# hello44Leo.net
KiCad netlist of a schematic drawn in EAGLE
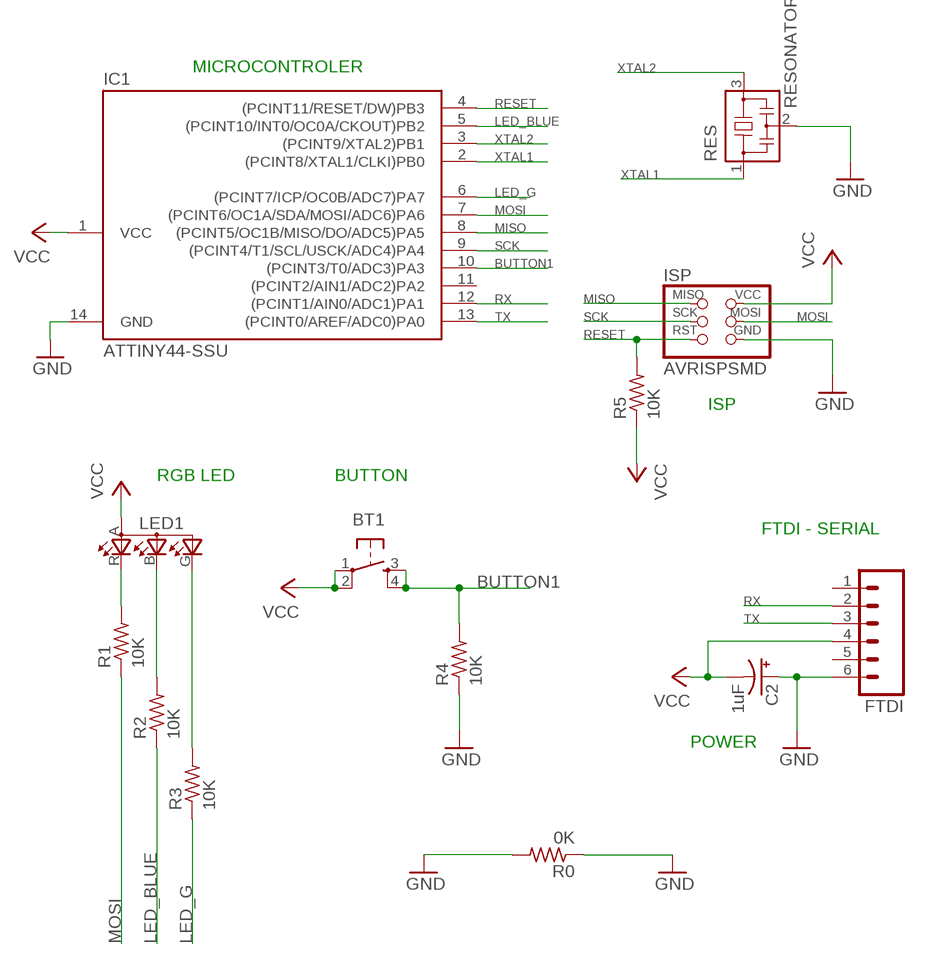
[diagram p0: schematic, sheet 1]

(export (version "E")
  (design (tool "Eeschema 10.0.6"))
  (components
    (comp (ref "BT1")
      (value "6MM_SWITCH6MM_SWITCH")
      (footprint "eagle-import:6MM_SWITCH")
      (libsource (lib "eagle-import") (part "6MM_SWITCH6MM_SWITCH"))
    )
    (comp (ref "C2")
      (value "1uF")
      (footprint "eagle-import:A3216-18")
      (libsource (lib "eagle-import") (part "POLARIZED_CAPACITORA3216-18"))
    )
    (comp (ref "FTDI")
      (value "M061X06-SMD_EDGE_FEMALE")
      (footprint "eagle-import:1X06-SMD_EDGE")
      (libsource (lib "eagle-import") (part "M061X06-SMD_EDGE_FEMALE"))
    )
    (comp (ref "IC1")
      (value "ATTINY44-SSU")
      (footprint "eagle-import:SOIC14")
      (libsource (lib "eagle-import") (part "ATTINY44-SSU"))
    )
    (comp (ref "ISP")
      (value "AVRISPSMD")
      (footprint "eagle-import:2X03SMD")
      (libsource (lib "eagle-import") (part "AVRISPSMD"))
    )
    (comp (ref "LED1")
      (value "LEDRGBOLD")
      (footprint "eagle-import:P-LCC-4-3")
      (libsource (lib "eagle-import") (part "LEDRGBOLD"))
    )
    (comp (ref "R0")
      (value "0K")
      (footprint "eagle-import:1206")
      (libsource (lib "eagle-import") (part "RESISTOR1206"))
    )
    (comp (ref "R1")
      (value "10K")
      (footprint "eagle-import:1206")
      (libsource (lib "eagle-import") (part "RESISTOR1206"))
    )
    (comp (ref "R2")
      (value "10K")
      (footprint "eagle-import:1206")
      (libsource (lib "eagle-import") (part "RESISTOR1206"))
    )
    (comp (ref "R3")
      (value "10K")
      (footprint "eagle-import:1206")
      (libsource (lib "eagle-import") (part "RESISTOR1206"))
    )
    (comp (ref "R4")
      (value "10K")
      (footprint "eagle-import:1206")
      (libsource (lib "eagle-import") (part "RESISTOR1206"))
    )
    (comp (ref "R5")
      (value "10K")
      (footprint "eagle-import:1206")
      (libsource (lib "eagle-import") (part "RESISTOR1206"))
    )
    (comp (ref "RES")
      (value "RESONATOR")
      (footprint "eagle-import:EFOBM")
      (libsource (lib "eagle-import") (part "RESONATOR"))
    )
  )
  (nets
    (net (code "1") (name "/BUTTON1") (class "Default")
      (node (ref "BT1") (pin "3") (pinfunction "S_3") (pintype "passive"))
      (node (ref "BT1") (pin "4") (pinfunction "S1_4") (pintype "passive"))
      (node (ref "IC1") (pin "10") (pinfunction "(PCINT3/T0/ADC3)PA3_10") (pintype "bidirectional"))
      (node (ref "R4") (pin "2") (pinfunction "2_2") (pintype "passive"))
    )
    (net (code "2") (name "/LED_BLUE") (class "Default")
      (node (ref "IC1") (pin "5") (pinfunction "(PCINT10/INT0/OC0A/CKOUT)PB2_5") (pintype "bidirectional"))
      (node (ref "R2") (pin "1") (pinfunction "1_1") (pintype "passive"))
    )
    (net (code "3") (name "/LED_G") (class "Default")
      (node (ref "IC1") (pin "6") (pinfunction "(PCINT7/ICP/OC0B/ADC7)PA7_6") (pintype "bidirectional"))
      (node (ref "R3") (pin "1") (pinfunction "1_1") (pintype "passive"))
    )
    (net (code "4") (name "/MISO") (class "Default")
      (node (ref "IC1") (pin "8") (pinfunction "(PCINT5/OC1B/MISO/DO/ADC5)PA5_8") (pintype "bidirectional"))
      (node (ref "ISP") (pin "1") (pinfunction "MISO_1") (pintype "passive"))
    )
    (net (code "5") (name "/MOSI") (class "Default")
      (node (ref "IC1") (pin "7") (pinfunction "(PCINT6/OC1A/SDA/MOSI/ADC6)PA6_7") (pintype "bidirectional"))
      (node (ref "ISP") (pin "4") (pinfunction "MOSI_4") (pintype "passive"))
      (node (ref "R1") (pin "1") (pinfunction "1_1") (pintype "passive"))
    )
    (net (code "6") (name "/RESET") (class "Default")
      (node (ref "IC1") (pin "4") (pinfunction "(PCINT11/RESET/DW)PB3_4") (pintype "bidirectional"))
      (node (ref "ISP") (pin "5") (pinfunction "RST_5") (pintype "passive"))
      (node (ref "R5") (pin "2") (pinfunction "2_2") (pintype "passive"))
    )
    (net (code "7") (name "/RX") (class "Default")
      (node (ref "FTDI") (pin "2") (pinfunction "2_2") (pintype "passive"))
      (node (ref "IC1") (pin "12") (pinfunction "(PCINT1/AIN0/ADC1)PA1_12") (pintype "bidirectional"))
    )
    (net (code "8") (name "/SCK") (class "Default")
      (node (ref "IC1") (pin "9") (pinfunction "(PCINT4/T1/SCL/USCK/ADC4)PA4_9") (pintype "bidirectional"))
      (node (ref "ISP") (pin "3") (pinfunction "SCK_3") (pintype "passive"))
    )
    (net (code "9") (name "/TX") (class "Default")
      (node (ref "FTDI") (pin "3") (pinfunction "3_3") (pintype "passive"))
      (node (ref "IC1") (pin "13") (pinfunction "(PCINT0/AREF/ADC0)PA0_13") (pintype "bidirectional"))
    )
    (net (code "10") (name "/XTAL1") (class "Default")
      (node (ref "IC1") (pin "2") (pinfunction "(PCINT8/XTAL1/CLKI)PB0_2") (pintype "bidirectional"))
      (node (ref "RES") (pin "1") (pinfunction "1_1") (pintype "passive"))
    )
    (net (code "11") (name "/XTAL2") (class "Default")
      (node (ref "IC1") (pin "3") (pinfunction "(PCINT9/XTAL2)PB1_3") (pintype "bidirectional"))
      (node (ref "RES") (pin "3") (pinfunction "3_3") (pintype "passive"))
    )
    (net (code "12") (name "GND") (class "Default")
      (node (ref "C2") (pin "+") (pinfunction "+_+") (pintype "passive"))
      (node (ref "FTDI") (pin "6") (pinfunction "6_6") (pintype "passive"))
      (node (ref "IC1") (pin "14") (pinfunction "GND_14") (pintype "power_in"))
      (node (ref "ISP") (pin "6") (pinfunction "GND_6") (pintype "passive"))
      (node (ref "R0") (pin "1") (pinfunction "1_1") (pintype "passive"))
      (node (ref "R0") (pin "2") (pinfunction "2_2") (pintype "passive"))
      (node (ref "R4") (pin "1") (pinfunction "1_1") (pintype "passive"))
      (node (ref "RES") (pin "2") (pinfunction "2_2") (pintype "passive"))
    )
    (net (code "13") (name "Net-(LED1-CBLUE)") (class "Default")
      (node (ref "LED1") (pin "B") (pinfunction "CBLUE_B") (pintype "passive"))
      (node (ref "R2") (pin "2") (pinfunction "2_2") (pintype "passive"))
    )
    (net (code "14") (name "Net-(LED1-CGREEN)") (class "Default")
      (node (ref "LED1") (pin "G") (pinfunction "CGREEN_G") (pintype "passive"))
      (node (ref "R3") (pin "2") (pinfunction "2_2") (pintype "passive"))
    )
    (net (code "15") (name "Net-(LED1-CRED)") (class "Default")
      (node (ref "LED1") (pin "R") (pinfunction "CRED_R") (pintype "passive"))
      (node (ref "R1") (pin "2") (pinfunction "2_2") (pintype "passive"))
    )
    (net (code "16") (name "VCC") (class "Default")
      (node (ref "BT1") (pin "1") (pinfunction "P_1") (pintype "passive"))
      (node (ref "BT1") (pin "2") (pinfunction "P1_2") (pintype "passive"))
      (node (ref "C2") (pin "-") (pinfunction "-_-") (pintype "passive"))
      (node (ref "FTDI") (pin "4") (pinfunction "4_4") (pintype "passive"))
      (node (ref "IC1") (pin "1") (pinfunction "VCC_1") (pintype "power_in"))
      (node (ref "ISP") (pin "2") (pinfunction "VCC_2") (pintype "passive"))
      (node (ref "LED1") (pin "A") (pinfunction "A2_A") (pintype "passive"))
      (node (ref "R5") (pin "1") (pinfunction "1_1") (pintype "passive"))
    )
    (net (code "17") (name "unconnected-(FTDI-Pad1)") (class "Default")
      (node (ref "FTDI") (pin "1") (pinfunction "1_1") (pintype "passive"))
    )
    (net (code "18") (name "unconnected-(FTDI-Pad5)") (class "Default")
      (node (ref "FTDI") (pin "5") (pinfunction "5_5") (pintype "passive"))
    )
    (net (code "19") (name "unconnected-(IC1-(PCINT2{slash}AIN1{slash}ADC2)PA2-Pad11)") (class "Default")
      (node (ref "IC1") (pin "11") (pinfunction "(PCINT2/AIN1/ADC2)PA2_11") (pintype "bidirectional"))
    )
  )
)
